# satshakit.net
KiCad netlist of a schematic drawn in EAGLE
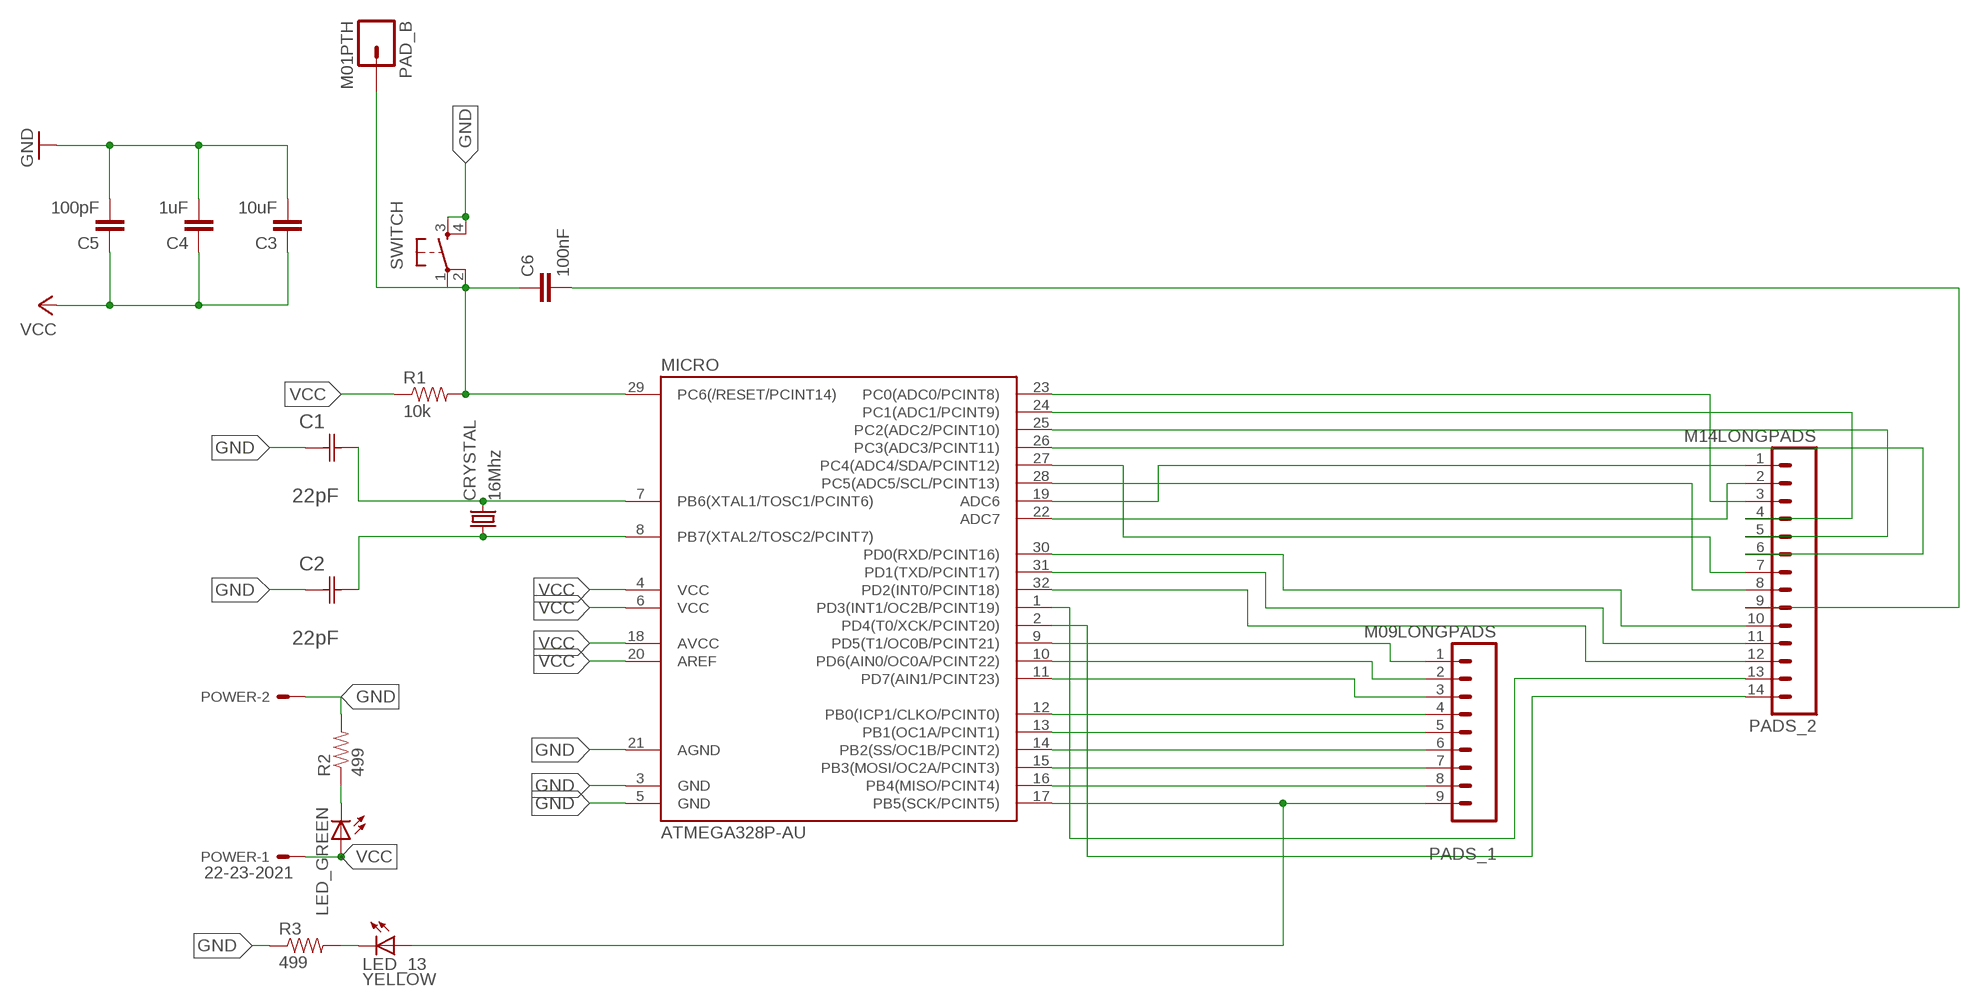
[diagram p0: schematic, sheet 1]

(export (version "E")
  (design (tool "Eeschema 10.0.6"))
  (components
    (comp (ref "C1")
      (value "22pF")
      (footprint "eagle-import:CAPC3216X178N")
      (fields (field (name "MPN") "0612ZC225MAT2A") (field (name "TOLERANCE") "±20%"))
      (libsource (lib "eagle-import") (part "0612ZC225MAT2A"))
    )
    (comp (ref "C2")
      (value "22pF")
      (footprint "eagle-import:CAPC3216X178N")
      (fields (field (name "MPN") "0612ZC225MAT2A") (field (name "TOLERANCE") "±20%"))
      (libsource (lib "eagle-import") (part "0612ZC225MAT2A"))
    )
    (comp (ref "C3")
      (value "10uF")
      (footprint "eagle-import:1206")
      (libsource (lib "eagle-import") (part "CAP1206"))
    )
    (comp (ref "C4")
      (value "1uF")
      (footprint "eagle-import:1206")
      (libsource (lib "eagle-import") (part "CAP1206"))
    )
    (comp (ref "C5")
      (value "100pF")
      (footprint "eagle-import:1206")
      (libsource (lib "eagle-import") (part "CAP1206"))
    )
    (comp (ref "C6")
      (value "100nF")
      (footprint "eagle-import:1206")
      (libsource (lib "eagle-import") (part "CAP1206"))
    )
    (comp (ref "CRYSTAL")
      (value "16Mhz")
      (footprint "eagle-import:CSM-7X-DU")
      (libsource (lib "eagle-import") (part "CSM-7X-DU"))
    )
    (comp (ref "LED_13")
      (value "YELLOW")
      (footprint "eagle-import:1206")
      (libsource (lib "eagle-import") (part "LED1206"))
    )
    (comp (ref "LED_GREEN")
      (value "LED1206")
      (footprint "eagle-import:1206")
      (libsource (lib "eagle-import") (part "LED1206"))
    )
    (comp (ref "MICRO")
      (value "ATMEGA328P-AU")
      (footprint "eagle-import:TQFP32-08")
      (libsource (lib "eagle-import") (part "ATMEGA48/88/168-AU"))
    )
    (comp (ref "PADS_1")
      (value "M09LONGPADS")
      (footprint "eagle-import:1X09_LONGPADS")
      (libsource (lib "eagle-import") (part "M09LONGPADS"))
    )
    (comp (ref "PADS_2")
      (value "M14LONGPADS")
      (footprint "eagle-import:1X14-LONGPADS")
      (libsource (lib "eagle-import") (part "M14LONGPADS"))
    )
    (comp (ref "PAD_B")
      (value "M01PTH")
      (footprint "eagle-import:1X01")
      (libsource (lib "eagle-import") (part "M01PTH"))
    )
    (comp (ref "POWER")
      (value "22-23-2021")
      (footprint "eagle-import:22-23-2021")
      (fields (field (name "MF") "MOLEX"))
      (libsource (lib "eagle-import") (part "22-23-2021"))
    )
    (comp (ref "R1")
      (value "10k")
      (footprint "eagle-import:1206")
      (libsource (lib "eagle-import") (part "RESISTOR1206"))
    )
    (comp (ref "R2")
      (value "499")
      (footprint "eagle-import:1206")
      (libsource (lib "eagle-import") (part "RESISTOR1206"))
    )
    (comp (ref "R3")
      (value "499")
      (footprint "eagle-import:1206")
      (libsource (lib "eagle-import") (part "RESISTOR1206"))
    )
    (comp (ref "SWITCH")
      (value "6MM_SWITCH6MM_SWITCH")
      (footprint "eagle-import:6MM_SWITCH")
      (libsource (lib "eagle-import") (part "6MM_SWITCH6MM_SWITCH"))
    )
  )
  (nets
    (net (code "1") (name "GND") (class "Default")
      (node (ref "C1") (pin "1") (pinfunction "C1_1") (pintype "passive"))
      (node (ref "C2") (pin "1") (pinfunction "C1_1") (pintype "passive"))
      (node (ref "C3") (pin "2") (pinfunction "2_2") (pintype "passive"))
      (node (ref "C4") (pin "2") (pinfunction "2_2") (pintype "passive"))
      (node (ref "C5") (pin "2") (pinfunction "2_2") (pintype "passive"))
      (node (ref "MICRO") (pin "21") (pinfunction "AGND_21") (pintype "power_in"))
      (node (ref "MICRO") (pin "3") (pinfunction "GND_3") (pintype "power_in"))
      (node (ref "MICRO") (pin "5") (pinfunction "GND_5") (pintype "power_in"))
      (node (ref "POWER") (pin "2") (pinfunction "S_2") (pintype "passive"))
      (node (ref "R2") (pin "2") (pinfunction "2_2") (pintype "passive"))
      (node (ref "R3") (pin "1") (pinfunction "1_1") (pintype "passive"))
      (node (ref "SWITCH") (pin "3") (pinfunction "S_3") (pintype "passive"))
      (node (ref "SWITCH") (pin "4") (pinfunction "S1_4") (pintype "passive"))
    )
    (net (code "2") (name "Net-(C1-C2)") (class "Default")
      (node (ref "C1") (pin "2") (pinfunction "C2_2") (pintype "passive"))
      (node (ref "CRYSTAL") (pin "2") (pinfunction "2_2") (pintype "passive"))
      (node (ref "MICRO") (pin "7") (pinfunction "PB6(XTAL1/TOSC1/PCINT6)_7") (pintype "bidirectional"))
    )
    (net (code "3") (name "Net-(C2-C2)") (class "Default")
      (node (ref "C2") (pin "2") (pinfunction "C2_2") (pintype "passive"))
      (node (ref "CRYSTAL") (pin "1") (pinfunction "1_1") (pintype "passive"))
      (node (ref "MICRO") (pin "8") (pinfunction "PB7(XTAL2/TOSC2/PCINT7)_8") (pintype "bidirectional"))
    )
    (net (code "4") (name "Net-(C6-Pad2)") (class "Default")
      (node (ref "C6") (pin "2") (pinfunction "2_2") (pintype "passive"))
      (node (ref "PADS_2") (pin "9") (pinfunction "9_9") (pintype "passive"))
    )
    (net (code "5") (name "Net-(LED_13-A)") (class "Default")
      (node (ref "LED_13") (pin "1") (pinfunction "A_1") (pintype "passive"))
      (node (ref "MICRO") (pin "17") (pinfunction "PB5(SCK/PCINT5)_17") (pintype "bidirectional"))
      (node (ref "PADS_1") (pin "9") (pinfunction "9_9") (pintype "passive"))
    )
    (net (code "6") (name "Net-(LED_13-C)") (class "Default")
      (node (ref "LED_13") (pin "2") (pinfunction "C_2") (pintype "passive"))
      (node (ref "R3") (pin "2") (pinfunction "2_2") (pintype "passive"))
    )
    (net (code "7") (name "Net-(LED_GREEN-C)") (class "Default")
      (node (ref "LED_GREEN") (pin "2") (pinfunction "C_2") (pintype "passive"))
      (node (ref "R2") (pin "1") (pinfunction "1_1") (pintype "passive"))
    )
    (net (code "8") (name "Net-(MICRO-ADC6)") (class "Default")
      (node (ref "MICRO") (pin "19") (pinfunction "ADC6_19") (pintype "passive"))
      (node (ref "PADS_2") (pin "1") (pinfunction "1_1") (pintype "passive"))
    )
    (net (code "9") (name "Net-(MICRO-ADC7)") (class "Default")
      (node (ref "MICRO") (pin "22") (pinfunction "ADC7_22") (pintype "passive"))
      (node (ref "PADS_2") (pin "2") (pinfunction "2_2") (pintype "passive"))
    )
    (net (code "10") (name "Net-(MICRO-PB0(ICP1{slash}CLKO{slash}PCINT0))") (class "Default")
      (node (ref "MICRO") (pin "12") (pinfunction "PB0(ICP1/CLKO/PCINT0)_12") (pintype "bidirectional"))
      (node (ref "PADS_1") (pin "4") (pinfunction "4_4") (pintype "passive"))
    )
    (net (code "11") (name "Net-(MICRO-PB1(OC1A{slash}PCINT1))") (class "Default")
      (node (ref "MICRO") (pin "13") (pinfunction "PB1(OC1A/PCINT1)_13") (pintype "bidirectional"))
      (node (ref "PADS_1") (pin "5") (pinfunction "5_5") (pintype "passive"))
    )
    (net (code "12") (name "Net-(MICRO-PB2(SS{slash}OC1B{slash}PCINT2))") (class "Default")
      (node (ref "MICRO") (pin "14") (pinfunction "PB2(SS/OC1B/PCINT2)_14") (pintype "bidirectional"))
      (node (ref "PADS_1") (pin "6") (pinfunction "6_6") (pintype "passive"))
    )
    (net (code "13") (name "Net-(MICRO-PB3(MOSI{slash}OC2A{slash}PCINT3))") (class "Default")
      (node (ref "MICRO") (pin "15") (pinfunction "PB3(MOSI/OC2A/PCINT3)_15") (pintype "bidirectional"))
      (node (ref "PADS_1") (pin "7") (pinfunction "7_7") (pintype "passive"))
    )
    (net (code "14") (name "Net-(MICRO-PB4(MISO{slash}PCINT4))") (class "Default")
      (node (ref "MICRO") (pin "16") (pinfunction "PB4(MISO/PCINT4)_16") (pintype "bidirectional"))
      (node (ref "PADS_1") (pin "8") (pinfunction "8_8") (pintype "passive"))
    )
    (net (code "15") (name "Net-(MICRO-PC0(ADC0{slash}PCINT8))") (class "Default")
      (node (ref "MICRO") (pin "23") (pinfunction "PC0(ADC0/PCINT8)_23") (pintype "bidirectional"))
      (node (ref "PADS_2") (pin "3") (pinfunction "3_3") (pintype "passive"))
    )
    (net (code "16") (name "Net-(MICRO-PC1(ADC1{slash}PCINT9))") (class "Default")
      (node (ref "MICRO") (pin "24") (pinfunction "PC1(ADC1/PCINT9)_24") (pintype "bidirectional"))
      (node (ref "PADS_2") (pin "4") (pinfunction "4_4") (pintype "passive"))
    )
    (net (code "17") (name "Net-(MICRO-PC2(ADC2{slash}PCINT10))") (class "Default")
      (node (ref "MICRO") (pin "25") (pinfunction "PC2(ADC2/PCINT10)_25") (pintype "bidirectional"))
      (node (ref "PADS_2") (pin "5") (pinfunction "5_5") (pintype "passive"))
    )
    (net (code "18") (name "Net-(MICRO-PC3(ADC3{slash}PCINT11))") (class "Default")
      (node (ref "MICRO") (pin "26") (pinfunction "PC3(ADC3/PCINT11)_26") (pintype "bidirectional"))
      (node (ref "PADS_2") (pin "6") (pinfunction "6_6") (pintype "passive"))
    )
    (net (code "19") (name "Net-(MICRO-PC4(ADC4{slash}SDA{slash}PCINT12))") (class "Default")
      (node (ref "MICRO") (pin "27") (pinfunction "PC4(ADC4/SDA/PCINT12)_27") (pintype "bidirectional"))
      (node (ref "PADS_2") (pin "7") (pinfunction "7_7") (pintype "passive"))
    )
    (net (code "20") (name "Net-(MICRO-PC5(ADC5{slash}SCL{slash}PCINT13))") (class "Default")
      (node (ref "MICRO") (pin "28") (pinfunction "PC5(ADC5/SCL/PCINT13)_28") (pintype "bidirectional"))
      (node (ref "PADS_2") (pin "8") (pinfunction "8_8") (pintype "passive"))
    )
    (net (code "21") (name "Net-(MICRO-PC6({slash}RESET{slash}PCINT14))") (class "Default")
      (node (ref "C6") (pin "1") (pinfunction "1_1") (pintype "passive"))
      (node (ref "MICRO") (pin "29") (pinfunction "PC6(/RESET/PCINT14)_29") (pintype "bidirectional"))
      (node (ref "PAD_B") (pin "1") (pinfunction "1_1") (pintype "passive"))
      (node (ref "R1") (pin "2") (pinfunction "2_2") (pintype "passive"))
      (node (ref "SWITCH") (pin "1") (pinfunction "P_1") (pintype "passive"))
      (node (ref "SWITCH") (pin "2") (pinfunction "P1_2") (pintype "passive"))
    )
    (net (code "22") (name "Net-(MICRO-PD0(RXD{slash}PCINT16))") (class "Default")
      (node (ref "MICRO") (pin "30") (pinfunction "PD0(RXD/PCINT16)_30") (pintype "bidirectional"))
      (node (ref "PADS_2") (pin "10") (pinfunction "10_10") (pintype "passive"))
    )
    (net (code "23") (name "Net-(MICRO-PD1(TXD{slash}PCINT17))") (class "Default")
      (node (ref "MICRO") (pin "31") (pinfunction "PD1(TXD/PCINT17)_31") (pintype "bidirectional"))
      (node (ref "PADS_2") (pin "11") (pinfunction "11_11") (pintype "passive"))
    )
    (net (code "24") (name "Net-(MICRO-PD2(INT0{slash}PCINT18))") (class "Default")
      (node (ref "MICRO") (pin "32") (pinfunction "PD2(INT0/PCINT18)_32") (pintype "bidirectional"))
      (node (ref "PADS_2") (pin "12") (pinfunction "12_12") (pintype "passive"))
    )
    (net (code "25") (name "Net-(MICRO-PD3(INT1{slash}OC2B{slash}PCINT19))") (class "Default")
      (node (ref "MICRO") (pin "1") (pinfunction "PD3(INT1/OC2B/PCINT19)_1") (pintype "bidirectional"))
      (node (ref "PADS_2") (pin "13") (pinfunction "13_13") (pintype "passive"))
    )
    (net (code "26") (name "Net-(MICRO-PD4(T0{slash}XCK{slash}PCINT20))") (class "Default")
      (node (ref "MICRO") (pin "2") (pinfunction "PD4(T0/XCK/PCINT20)_2") (pintype "bidirectional"))
      (node (ref "PADS_2") (pin "14") (pinfunction "14_14") (pintype "passive"))
    )
    (net (code "27") (name "Net-(MICRO-PD5(T1{slash}OC0B{slash}PCINT21))") (class "Default")
      (node (ref "MICRO") (pin "9") (pinfunction "PD5(T1/OC0B/PCINT21)_9") (pintype "bidirectional"))
      (node (ref "PADS_1") (pin "1") (pinfunction "1_1") (pintype "passive"))
    )
    (net (code "28") (name "Net-(MICRO-PD6(AIN0{slash}OC0A{slash}PCINT22))") (class "Default")
      (node (ref "MICRO") (pin "10") (pinfunction "PD6(AIN0/OC0A/PCINT22)_10") (pintype "bidirectional"))
      (node (ref "PADS_1") (pin "2") (pinfunction "2_2") (pintype "passive"))
    )
    (net (code "29") (name "Net-(MICRO-PD7(AIN1{slash}PCINT23))") (class "Default")
      (node (ref "MICRO") (pin "11") (pinfunction "PD7(AIN1/PCINT23)_11") (pintype "bidirectional"))
      (node (ref "PADS_1") (pin "3") (pinfunction "3_3") (pintype "passive"))
    )
    (net (code "30") (name "VCC") (class "Default")
      (node (ref "C3") (pin "1") (pinfunction "1_1") (pintype "passive"))
      (node (ref "C4") (pin "1") (pinfunction "1_1") (pintype "passive"))
      (node (ref "C5") (pin "1") (pinfunction "1_1") (pintype "passive"))
      (node (ref "LED_GREEN") (pin "1") (pinfunction "A_1") (pintype "passive"))
      (node (ref "MICRO") (pin "18") (pinfunction "AVCC_18") (pintype "passive"))
      (node (ref "MICRO") (pin "20") (pinfunction "AREF_20") (pintype "passive"))
      (node (ref "MICRO") (pin "4") (pinfunction "VCC_4") (pintype "power_in"))
      (node (ref "MICRO") (pin "6") (pinfunction "VCC_6") (pintype "power_in"))
      (node (ref "POWER") (pin "1") (pinfunction "S_1") (pintype "passive"))
      (node (ref "R1") (pin "1") (pinfunction "1_1") (pintype "passive"))
    )
  )
)
